# kolrs868_tx.net
KiCad netlist of a schematic drawn in EAGLE
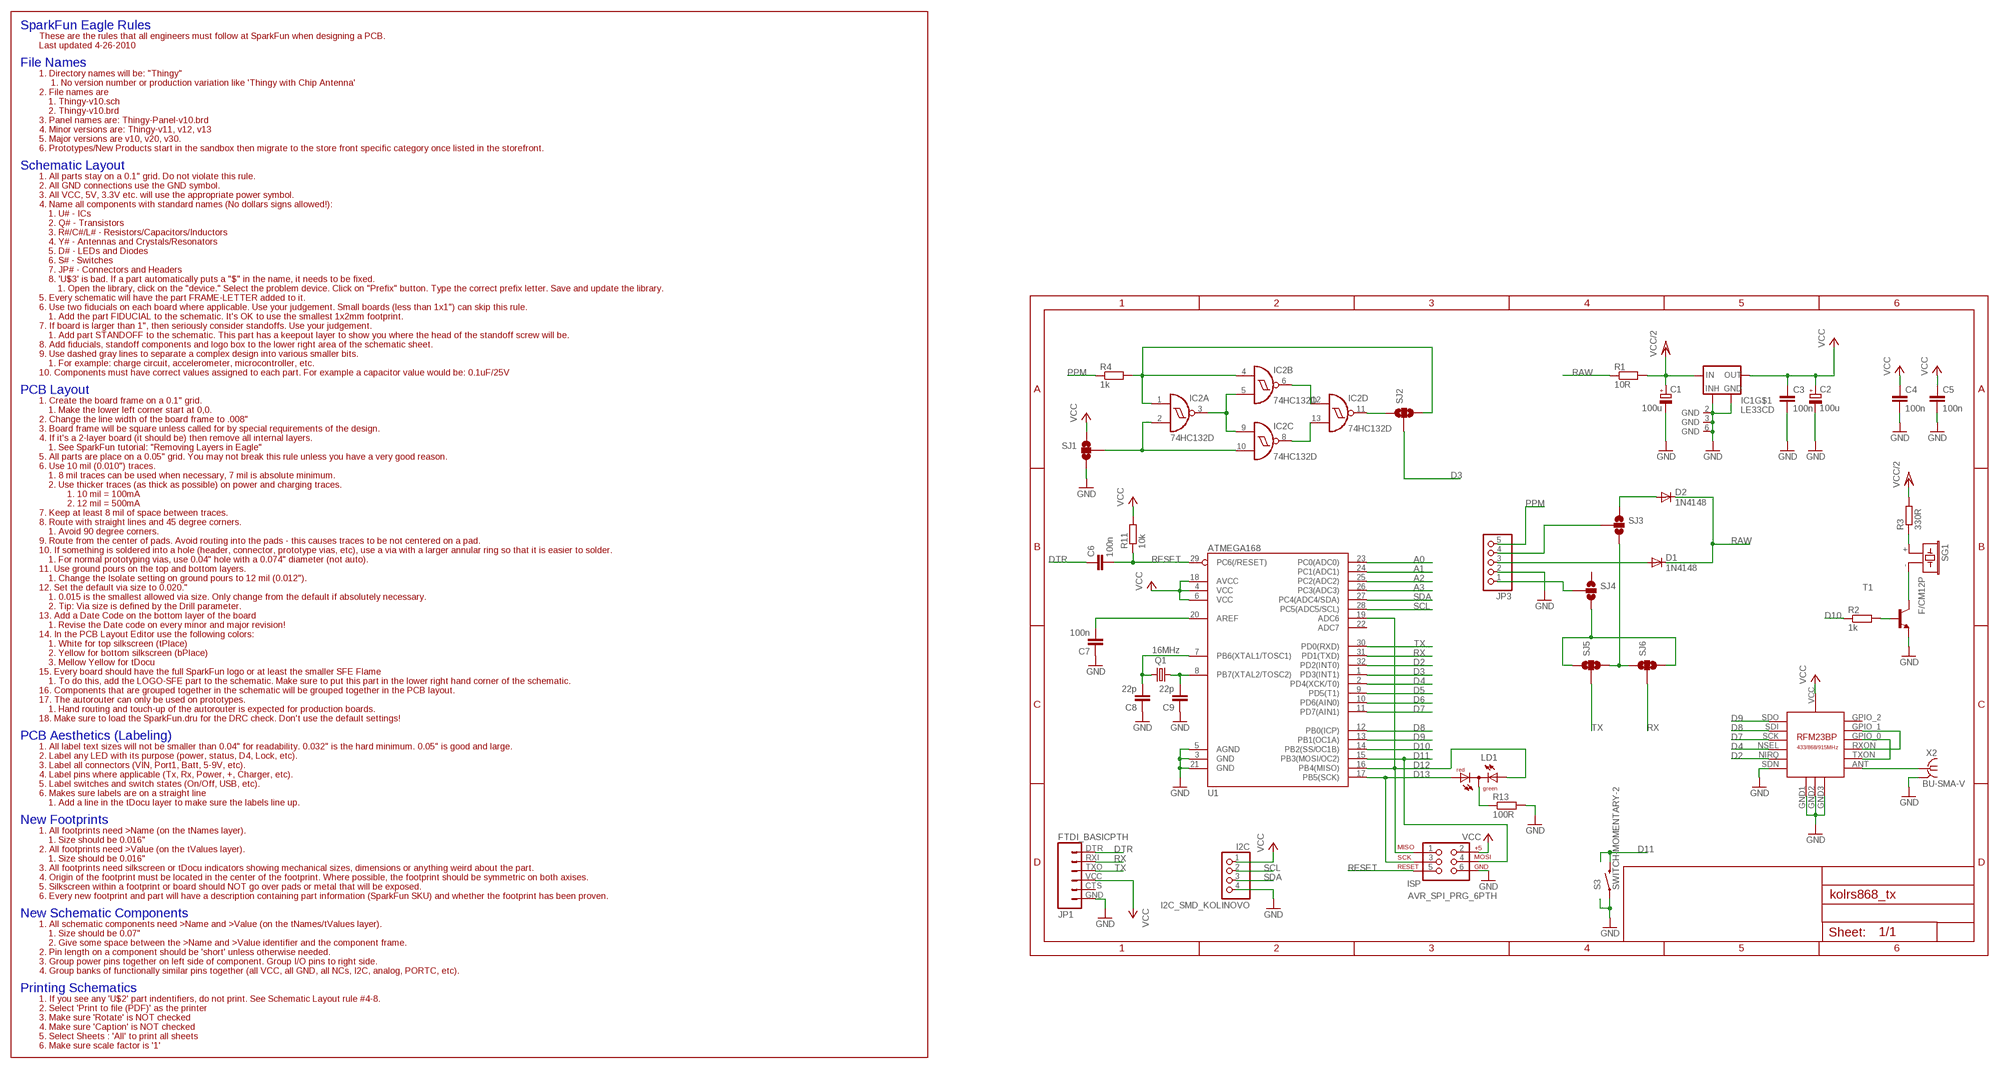
[diagram p0: schematic, sheet 1]

(export (version "E")
  (design (tool "Eeschema 10.0.6"))
  (components
    (comp (ref "C1")
      (value "100u")
      (footprint "eagle-import:SMC_B")
      (libsource (lib "eagle-import") (part "CPOL-EUSMCB"))
    )
    (comp (ref "C2")
      (value "100u")
      (footprint "eagle-import:SMC_B")
      (libsource (lib "eagle-import") (part "CPOL-EUSMCB"))
    )
    (comp (ref "C3")
      (value "100n")
      (footprint "eagle-import:M0805")
      (libsource (lib "eagle-import") (part "C-EU_KOLIN"))
    )
    (comp (ref "C4")
      (value "100n")
      (footprint "eagle-import:M0805")
      (libsource (lib "eagle-import") (part "C-EU_KOLIN"))
    )
    (comp (ref "C5")
      (value "100n")
      (footprint "eagle-import:M0805")
      (libsource (lib "eagle-import") (part "C-EU_KOLIN"))
    )
    (comp (ref "C6")
      (value "100n")
      (footprint "eagle-import:M0805")
      (libsource (lib "eagle-import") (part "C-EU_KOLIN"))
    )
    (comp (ref "C7")
      (value "100n")
      (footprint "eagle-import:M0805")
      (libsource (lib "eagle-import") (part "C-EU_KOLIN"))
    )
    (comp (ref "C8")
      (value "22p")
      (footprint "eagle-import:M0805")
      (libsource (lib "eagle-import") (part "C-EU_KOLIN"))
    )
    (comp (ref "C9")
      (value "22p")
      (footprint "eagle-import:M0805")
      (libsource (lib "eagle-import") (part "C-EU_KOLIN"))
    )
    (comp (ref "D1")
      (value "1N4148")
      (footprint "eagle-import:MINIMELF")
      (libsource (lib "eagle-import") (part "DIODE-MINIMELF"))
    )
    (comp (ref "D2")
      (value "1N4148")
      (footprint "eagle-import:MINIMELF")
      (libsource (lib "eagle-import") (part "DIODE-MINIMELF"))
    )
    (comp (ref "I2C")
      (value "I2C_SMD_KOLINOVO")
      (footprint "eagle-import:1X04")
      (libsource (lib "eagle-import") (part "I2C_SMD_KOLINOVO"))
    )
    (comp (ref "IC1")
      (value "LE33CD")
      (footprint "eagle-import:SO8")
      (libsource (lib "eagle-import") (part "LE33CD"))
    )
    (comp (ref "IC2")
      (value "74HC132D")
      (footprint "eagle-import:SO14")
      (libsource (lib "eagle-import") (part "74132DHC"))
    )
    (comp (ref "ISP")
      (value "AVR_SPI_PRG_6PTH")
      (footprint "eagle-import:2X3")
      (libsource (lib "eagle-import") (part "AVR_SPI_PRG_6PTH"))
    )
    (comp (ref "JP1")
      (value "FTDI_BASICPTH")
      (footprint "eagle-import:FTDI_BASIC")
      (libsource (lib "eagle-import") (part "FTDI_BASICPTH"))
    )
    (comp (ref "JP3")
      (value "PINHD-1X5")
      (footprint "eagle-import:1X05")
      (libsource (lib "eagle-import") (part "PINHD-1X5"))
    )
    (comp (ref "LD1")
      (value "DUOLED-RG-C")
      (footprint "eagle-import:DUOLED-C-5MM")
      (libsource (lib "eagle-import") (part "DUOLED-RG-C"))
    )
    (comp (ref "Q1")
      (value "16MHz")
      (footprint "eagle-import:HC49UP")
      (libsource (lib "eagle-import") (part "CRYSTALHC49UP"))
    )
    (comp (ref "R1")
      (value "10R")
      (footprint "eagle-import:M0805")
      (libsource (lib "eagle-import") (part "R-EU_KOLINM0805"))
    )
    (comp (ref "R2")
      (value "1k")
      (footprint "eagle-import:M0805")
      (libsource (lib "eagle-import") (part "R-EU_KOLINM0805"))
    )
    (comp (ref "R3")
      (value "330R")
      (footprint "eagle-import:M0805")
      (libsource (lib "eagle-import") (part "R-EU_KOLINM0805"))
    )
    (comp (ref "R4")
      (value "1k")
      (footprint "eagle-import:M0805")
      (libsource (lib "eagle-import") (part "R-EU_KOLINM0805"))
    )
    (comp (ref "R11")
      (value "10k")
      (footprint "eagle-import:M0805")
      (libsource (lib "eagle-import") (part "R-EU_KOLINM0805"))
    )
    (comp (ref "R13")
      (value "100R")
      (footprint "eagle-import:M0805")
      (libsource (lib "eagle-import") (part "R-EU_KOLINM0805"))
    )
    (comp (ref "S3")
      (value "SWITCH-MOMENTARY-2")
      (footprint "eagle-import:TACTILE_SWITCH_TALL")
      (libsource (lib "eagle-import") (part "SWITCH-MOMENTARY-2"))
    )
    (comp (ref "SG1")
      (value "F/CM12P")
      (footprint "eagle-import:F_CM12P")
      (libsource (lib "eagle-import") (part "F/CM12P"))
    )
    (comp (ref "SJ1")
      (value "SOLDERJUMPER_2WAYS")
      (footprint "eagle-import:SJ_3")
      (libsource (lib "eagle-import") (part "SOLDERJUMPER_2WAYS"))
    )
    (comp (ref "SJ2")
      (value "SOLDERJUMPER_2WAYS")
      (footprint "eagle-import:SJ_3")
      (libsource (lib "eagle-import") (part "SOLDERJUMPER_2WAYS"))
    )
    (comp (ref "SJ3")
      (value "SOLDERJUMPER_2WAYS")
      (footprint "eagle-import:SJ_3")
      (libsource (lib "eagle-import") (part "SOLDERJUMPER_2WAYS"))
    )
    (comp (ref "SJ4")
      (value "SOLDERJUMPER_2WAYS")
      (footprint "eagle-import:SJ_3")
      (libsource (lib "eagle-import") (part "SOLDERJUMPER_2WAYS"))
    )
    (comp (ref "SJ5")
      (value "SOLDERJUMPER_2WAYS")
      (footprint "eagle-import:SJ_3")
      (libsource (lib "eagle-import") (part "SOLDERJUMPER_2WAYS"))
    )
    (comp (ref "SJ6")
      (value "SOLDERJUMPER_2WAYS")
      (footprint "eagle-import:SJ_3")
      (libsource (lib "eagle-import") (part "SOLDERJUMPER_2WAYS"))
    )
    (comp (ref "T1")
      (value "BC848-NPN-SOT23-BEC")
      (footprint "eagle-import:SOT23-BEC")
      (libsource (lib "eagle-import") (part "-NPN-SOT23-BECBC848"))
    )
    (comp (ref "U$3")
      (value "RFM23BP")
      (footprint "eagle-import:RFM23BP")
      (libsource (lib "eagle-import") (part "RFM23BP"))
    )
    (comp (ref "U1")
      (value "ATMEGA168")
      (footprint "eagle-import:TQFP32-08")
      (libsource (lib "eagle-import") (part "ATMEGA168"))
    )
    (comp (ref "X2")
      (value "BU-SMA-V")
      (footprint "eagle-import:BU-SMA-V")
      (libsource (lib "eagle-import") (part "BU-SMA-V"))
    )
  )
  (nets
    (net (code "1") (name "/A0") (class "Default")
      (node (ref "U1") (pin "23") (pinfunction "PC0(ADC0)_23") (pintype "bidirectional"))
    )
    (net (code "2") (name "/A1") (class "Default")
      (node (ref "U1") (pin "24") (pinfunction "PC1(ADC1)_24") (pintype "bidirectional"))
    )
    (net (code "3") (name "/A2") (class "Default")
      (node (ref "U1") (pin "25") (pinfunction "PC2(ADC2)_25") (pintype "bidirectional"))
    )
    (net (code "4") (name "/A3") (class "Default")
      (node (ref "U1") (pin "26") (pinfunction "PC3(ADC3)_26") (pintype "bidirectional"))
    )
    (net (code "5") (name "/D2") (class "Default")
      (node (ref "U$3") (pin "NIRQ") (pinfunction "NIRQ_NIRQ") (pintype "bidirectional"))
      (node (ref "U1") (pin "32") (pinfunction "PD2(INT0)_32") (pintype "bidirectional"))
    )
    (net (code "6") (name "/D3") (class "Default")
      (node (ref "SJ2") (pin "2") (pinfunction "2_2") (pintype "passive"))
      (node (ref "U1") (pin "1") (pinfunction "PD3(INT1)_1") (pintype "bidirectional"))
    )
    (net (code "7") (name "/D4") (class "Default")
      (node (ref "U$3") (pin "NSEL") (pinfunction "NSEL_NSEL") (pintype "bidirectional"))
      (node (ref "U1") (pin "2") (pinfunction "PD4(XCK/T0)_2") (pintype "bidirectional"))
    )
    (net (code "8") (name "/D5") (class "Default")
      (node (ref "U1") (pin "9") (pinfunction "PD5(T1)_9") (pintype "bidirectional"))
    )
    (net (code "9") (name "/D6") (class "Default")
      (node (ref "U1") (pin "10") (pinfunction "PD6(AIN0)_10") (pintype "bidirectional"))
    )
    (net (code "10") (name "/D7") (class "Default")
      (node (ref "U$3") (pin "SCK") (pinfunction "SCK_SCK") (pintype "bidirectional"))
      (node (ref "U1") (pin "11") (pinfunction "PD7(AIN1)_11") (pintype "bidirectional"))
    )
    (net (code "11") (name "/D8") (class "Default")
      (node (ref "U$3") (pin "SDI") (pinfunction "SDI_SDI") (pintype "bidirectional"))
      (node (ref "U1") (pin "12") (pinfunction "PB0(ICP)_12") (pintype "bidirectional"))
    )
    (net (code "12") (name "/D9") (class "Default")
      (node (ref "U$3") (pin "SDO") (pinfunction "SDO_SDO") (pintype "bidirectional"))
      (node (ref "U1") (pin "13") (pinfunction "PB1(OC1A)_13") (pintype "bidirectional"))
    )
    (net (code "13") (name "/D10") (class "Default")
      (node (ref "R2") (pin "1") (pinfunction "1_1") (pintype "passive"))
      (node (ref "U1") (pin "14") (pinfunction "PB2(SS/OC1B)_14") (pintype "bidirectional"))
    )
    (net (code "14") (name "/D11") (class "Default")
      (node (ref "ISP") (pin "4") (pinfunction "4_4") (pintype "passive"))
      (node (ref "S3") (pin "B2") (pinfunction "2_B2") (pintype "passive"))
      (node (ref "U1") (pin "15") (pinfunction "PB3(MOSI/OC2)_15") (pintype "bidirectional"))
    )
    (net (code "15") (name "/D12") (class "Default")
      (node (ref "ISP") (pin "1") (pinfunction "1_1") (pintype "passive"))
      (node (ref "LD1") (pin "AX") (pinfunction "AG_AX") (pintype "passive"))
      (node (ref "U1") (pin "16") (pinfunction "PB4(MISO)_16") (pintype "bidirectional"))
      (node (ref "U1") (pin "19") (pinfunction "ADC6_19") (pintype "bidirectional"))
    )
    (net (code "16") (name "/D13") (class "Default")
      (node (ref "ISP") (pin "3") (pinfunction "3_3") (pintype "passive"))
      (node (ref "LD1") (pin "AR") (pinfunction "AR_AR") (pintype "passive"))
      (node (ref "U1") (pin "17") (pinfunction "PB5(SCK)_17") (pintype "bidirectional"))
    )
    (net (code "17") (name "/DTR") (class "Default")
      (node (ref "C6") (pin "1") (pinfunction "1_1") (pintype "passive"))
      (node (ref "JP1") (pin "DTR") (pinfunction "1_DTR") (pintype "passive"))
    )
    (net (code "18") (name "/PPM") (class "Default")
      (node (ref "JP3") (pin "5") (pinfunction "5_5") (pintype "passive"))
      (node (ref "R4") (pin "1") (pinfunction "1_1") (pintype "passive"))
    )
    (net (code "19") (name "/RAW") (class "Default")
      (node (ref "D1") (pin "C") (pinfunction "C_C") (pintype "passive"))
      (node (ref "D2") (pin "C") (pinfunction "C_C") (pintype "passive"))
      (node (ref "R1") (pin "1") (pinfunction "1_1") (pintype "passive"))
    )
    (net (code "20") (name "/RESET") (class "Default")
      (node (ref "C6") (pin "2") (pinfunction "2_2") (pintype "passive"))
      (node (ref "ISP") (pin "5") (pinfunction "5_5") (pintype "passive"))
      (node (ref "R11") (pin "1") (pinfunction "1_1") (pintype "passive"))
      (node (ref "U1") (pin "29") (pinfunction "PC6(/RESET)_29") (pintype "bidirectional"))
    )
    (net (code "21") (name "/RX") (class "Default")
      (node (ref "JP1") (pin "RXI") (pinfunction "2_RXI") (pintype "passive"))
      (node (ref "SJ6") (pin "2") (pinfunction "2_2") (pintype "passive"))
      (node (ref "U1") (pin "31") (pinfunction "PD1(TXD)_31") (pintype "bidirectional"))
    )
    (net (code "22") (name "/SCL") (class "Default")
      (node (ref "I2C") (pin "2") (pinfunction "2_2") (pintype "passive"))
      (node (ref "U1") (pin "28") (pinfunction "PC5(ADC5/SCL)_28") (pintype "bidirectional"))
    )
    (net (code "23") (name "/SDA") (class "Default")
      (node (ref "I2C") (pin "3") (pinfunction "3_3") (pintype "passive"))
      (node (ref "U1") (pin "27") (pinfunction "PC4(ADC4/SDA)_27") (pintype "bidirectional"))
    )
    (net (code "24") (name "/TX") (class "Default")
      (node (ref "JP1") (pin "TXO") (pinfunction "3_TXO") (pintype "passive"))
      (node (ref "SJ5") (pin "2") (pinfunction "2_2") (pintype "passive"))
      (node (ref "U1") (pin "30") (pinfunction "PD0(RXD)_30") (pintype "bidirectional"))
    )
    (net (code "25") (name "GND") (class "Default")
      (node (ref "C1") (pin "-") (pinfunction "-_-") (pintype "passive"))
      (node (ref "C2") (pin "-") (pinfunction "-_-") (pintype "passive"))
      (node (ref "C3") (pin "2") (pinfunction "2_2") (pintype "passive"))
      (node (ref "C4") (pin "2") (pinfunction "2_2") (pintype "passive"))
      (node (ref "C5") (pin "2") (pinfunction "2_2") (pintype "passive"))
      (node (ref "C7") (pin "1") (pinfunction "1_1") (pintype "passive"))
      (node (ref "C8") (pin "1") (pinfunction "1_1") (pintype "passive"))
      (node (ref "C9") (pin "1") (pinfunction "1_1") (pintype "passive"))
      (node (ref "I2C") (pin "4") (pinfunction "4_4") (pintype "passive"))
      (node (ref "IC1") (pin "2") (pinfunction "GND_2") (pintype "power_in"))
      (node (ref "IC1") (pin "3") (pinfunction "GND_3") (pintype "power_in"))
      (node (ref "IC1") (pin "5") (pinfunction "INHIBIT_5") (pintype "input"))
      (node (ref "IC1") (pin "6") (pinfunction "GND_6") (pintype "power_in"))
      (node (ref "IC1") (pin "7") (pinfunction "GND_7") (pintype "input"))
      (node (ref "ISP") (pin "6") (pinfunction "6_6") (pintype "passive"))
      (node (ref "JP1") (pin "GND") (pinfunction "6_GND") (pintype "passive"))
      (node (ref "JP3") (pin "2") (pinfunction "2_2") (pintype "passive"))
      (node (ref "R13") (pin "2") (pinfunction "2_2") (pintype "passive"))
      (node (ref "S3") (pin "A2") (pinfunction "1_A2") (pintype "passive"))
      (node (ref "SJ1") (pin "3") (pinfunction "3_3") (pintype "passive"))
      (node (ref "T1") (pin "E") (pinfunction "E_E") (pintype "passive"))
      (node (ref "U$3") (pin "GND1") (pinfunction "GND1_GND1") (pintype "power_in"))
      (node (ref "U$3") (pin "GND2") (pinfunction "GND2_GND2") (pintype "power_in"))
      (node (ref "U$3") (pin "GND3") (pinfunction "GND3_GND3") (pintype "power_in"))
      (node (ref "U$3") (pin "SDN") (pinfunction "SDN_SDN") (pintype "bidirectional"))
      (node (ref "U1") (pin "21") (pinfunction "GND_21") (pintype "bidirectional"))
      (node (ref "U1") (pin "3") (pinfunction "GND_3") (pintype "bidirectional"))
      (node (ref "U1") (pin "5") (pinfunction "AGND_5") (pintype "bidirectional"))
      (node (ref "X2") (pin "2") (pinfunction "GND_2") (pintype "power_in"))
    )
    (net (code "26") (name "Net-(D1-PadA)") (class "Default")
      (node (ref "D1") (pin "A") (pinfunction "A_A") (pintype "passive"))
      (node (ref "JP3") (pin "3") (pinfunction "3_3") (pintype "passive"))
    )
    (net (code "27") (name "Net-(D2-PadA)") (class "Default")
      (node (ref "D2") (pin "A") (pinfunction "A_A") (pintype "passive"))
      (node (ref "SJ3") (pin "1") (pinfunction "1_1") (pintype "passive"))
    )
    (net (code "28") (name "Net-(IC2A-I0)") (class "Default")
      (node (ref "IC2") (pin "1") (pinfunction "I0_1") (pintype "input"))
      (node (ref "IC2") (pin "4") (pinfunction "I0_4") (pintype "input"))
      (node (ref "R4") (pin "2") (pinfunction "2_2") (pintype "passive"))
      (node (ref "SJ2") (pin "3") (pinfunction "3_3") (pintype "passive"))
    )
    (net (code "29") (name "Net-(IC2A-I1)") (class "Default")
      (node (ref "IC2") (pin "10") (pinfunction "I1_10") (pintype "input"))
      (node (ref "IC2") (pin "2") (pinfunction "I1_2") (pintype "input"))
      (node (ref "SJ1") (pin "2") (pinfunction "2_2") (pintype "passive"))
    )
    (net (code "30") (name "Net-(IC2A-O)") (class "Default")
      (node (ref "IC2") (pin "3") (pinfunction "O_3") (pintype "output"))
      (node (ref "IC2") (pin "5") (pinfunction "I1_5") (pintype "input"))
      (node (ref "IC2") (pin "9") (pinfunction "I0_9") (pintype "input"))
    )
    (net (code "31") (name "Net-(IC2B-O)") (class "Default")
      (node (ref "IC2") (pin "12") (pinfunction "I0_12") (pintype "input"))
      (node (ref "IC2") (pin "6") (pinfunction "O_6") (pintype "output"))
    )
    (net (code "32") (name "Net-(IC2C-O)") (class "Default")
      (node (ref "IC2") (pin "13") (pinfunction "I1_13") (pintype "input"))
      (node (ref "IC2") (pin "8") (pinfunction "O_8") (pintype "output"))
    )
    (net (code "33") (name "Net-(IC2D-O)") (class "Default")
      (node (ref "IC2") (pin "11") (pinfunction "O_11") (pintype "output"))
      (node (ref "SJ2") (pin "1") (pinfunction "1_1") (pintype "passive"))
    )
    (net (code "34") (name "Net-(JP3-Pad1)") (class "Default")
      (node (ref "JP3") (pin "1") (pinfunction "1_1") (pintype "passive"))
      (node (ref "SJ4") (pin "2") (pinfunction "2_2") (pintype "passive"))
    )
    (net (code "35") (name "Net-(JP3-Pad4)") (class "Default")
      (node (ref "JP3") (pin "4") (pinfunction "4_4") (pintype "passive"))
      (node (ref "SJ3") (pin "2") (pinfunction "2_2") (pintype "passive"))
    )
    (net (code "36") (name "Net-(LD1-PadC)") (class "Default")
      (node (ref "LD1") (pin "C") (pinfunction "C_C") (pintype "passive"))
      (node (ref "R13") (pin "1") (pinfunction "1_1") (pintype "passive"))
    )
    (net (code "37") (name "Net-(R2-Pad2)") (class "Default")
      (node (ref "R2") (pin "2") (pinfunction "2_2") (pintype "passive"))
      (node (ref "T1") (pin "B") (pinfunction "B_B") (pintype "passive"))
    )
    (net (code "38") (name "Net-(SG1-1)") (class "Default")
      (node (ref "R3") (pin "1") (pinfunction "1_1") (pintype "passive"))
      (node (ref "SG1") (pin "+") (pinfunction "1_+") (pintype "passive"))
    )
    (net (code "39") (name "Net-(SG1-2)") (class "Default")
      (node (ref "SG1") (pin "-") (pinfunction "2_-") (pintype "passive"))
      (node (ref "T1") (pin "C") (pinfunction "C_C") (pintype "passive"))
    )
    (net (code "40") (name "Net-(SJ3-Pad3)") (class "Default")
      (node (ref "SJ3") (pin "3") (pinfunction "3_3") (pintype "passive"))
      (node (ref "SJ5") (pin "3") (pinfunction "3_3") (pintype "passive"))
      (node (ref "SJ6") (pin "1") (pinfunction "1_1") (pintype "passive"))
    )
    (net (code "41") (name "Net-(SJ4-Pad3)") (class "Default")
      (node (ref "SJ4") (pin "3") (pinfunction "3_3") (pintype "passive"))
      (node (ref "SJ5") (pin "1") (pinfunction "1_1") (pintype "passive"))
      (node (ref "SJ6") (pin "3") (pinfunction "3_3") (pintype "passive"))
    )
    (net (code "42") (name "Net-(U$3-PadANT)") (class "Default")
      (node (ref "U$3") (pin "ANT") (pinfunction "ANT_ANT") (pintype "bidirectional"))
      (node (ref "X2") (pin "1") (pinfunction "1_1") (pintype "passive"))
    )
    (net (code "43") (name "Net-(U$3-PadGPIO_0)") (class "Default")
      (node (ref "U$3") (pin "GPIO_0") (pinfunction "GPIO_0_GPIO_0") (pintype "bidirectional"))
      (node (ref "U$3") (pin "TXON") (pinfunction "TXON_TXON") (pintype "bidirectional"))
    )
    (net (code "44") (name "Net-(U$3-PadGPIO_1)") (class "Default")
      (node (ref "U$3") (pin "GPIO_1") (pinfunction "GPIO_1_GPIO_1") (pintype "bidirectional"))
      (node (ref "U$3") (pin "RXON") (pinfunction "RXON_RXON") (pintype "bidirectional"))
    )
    (net (code "45") (name "Net-(U1-AREF)") (class "Default")
      (node (ref "C7") (pin "2") (pinfunction "2_2") (pintype "passive"))
      (node (ref "U1") (pin "20") (pinfunction "AREF_20") (pintype "bidirectional"))
    )
    (net (code "46") (name "Net-(U1-PB6(XTAL1{slash}TOSC1))") (class "Default")
      (node (ref "C8") (pin "2") (pinfunction "2_2") (pintype "passive"))
      (node (ref "Q1") (pin "2") (pinfunction "2_2") (pintype "passive"))
      (node (ref "U1") (pin "7") (pinfunction "PB6(XTAL1/TOSC1)_7") (pintype "bidirectional"))
    )
    (net (code "47") (name "Net-(U1-PB7(XTAL2{slash}TOSC2))") (class "Default")
      (node (ref "C9") (pin "2") (pinfunction "2_2") (pintype "passive"))
      (node (ref "Q1") (pin "1") (pinfunction "1_1") (pintype "passive"))
      (node (ref "U1") (pin "8") (pinfunction "PB7(XTAL2/TOSC2)_8") (pintype "bidirectional"))
    )
    (net (code "48") (name "VCC") (class "Default")
      (node (ref "C2") (pin "+") (pinfunction "+_+") (pintype "passive"))
      (node (ref "C3") (pin "1") (pinfunction "1_1") (pintype "passive"))
      (node (ref "C4") (pin "1") (pinfunction "1_1") (pintype "passive"))
      (node (ref "C5") (pin "1") (pinfunction "1_1") (pintype "passive"))
      (node (ref "I2C") (pin "1") (pinfunction "1_1") (pintype "passive"))
      (node (ref "IC1") (pin "1") (pinfunction "OUT_1") (pintype "passive"))
      (node (ref "ISP") (pin "2") (pinfunction "2_2") (pintype "passive"))
      (node (ref "JP1") (pin "VCC") (pinfunction "4_VCC") (pintype "passive"))
      (node (ref "R11") (pin "2") (pinfunction "2_2") (pintype "passive"))
      (node (ref "SJ1") (pin "1") (pinfunction "1_1") (pintype "passive"))
      (node (ref "U$3") (pin "VCC") (pinfunction "VCC_VCC") (pintype "power_in"))
      (node (ref "U1") (pin "18") (pinfunction "AVCC_18") (pintype "bidirectional"))
      (node (ref "U1") (pin "4") (pinfunction "VCC_4") (pintype "bidirectional"))
      (node (ref "U1") (pin "6") (pinfunction "VCC_6") (pintype "bidirectional"))
    )
    (net (code "49") (name "VCC{slash}2") (class "Default")
      (node (ref "C1") (pin "+") (pinfunction "+_+") (pintype "passive"))
      (node (ref "IC1") (pin "8") (pinfunction "IN_8") (pintype "input"))
      (node (ref "R1") (pin "2") (pinfunction "2_2") (pintype "passive"))
      (node (ref "R3") (pin "2") (pinfunction "2_2") (pintype "passive"))
    )
    (net (code "50") (name "unconnected-(JP1-5-PadCTS)") (class "Default")
      (node (ref "JP1") (pin "CTS") (pinfunction "5_CTS") (pintype "passive"))
    )
    (net (code "51") (name "unconnected-(SJ4-Pad1)") (class "Default")
      (node (ref "SJ4") (pin "1") (pinfunction "1_1") (pintype "passive"))
    )
    (net (code "52") (name "unconnected-(U$3-PadGPIO_2)") (class "Default")
      (node (ref "U$3") (pin "GPIO_2") (pinfunction "GPIO_2_GPIO_2") (pintype "bidirectional"))
    )
    (net (code "53") (name "unconnected-(U1-ADC7-Pad22)") (class "Default")
      (node (ref "U1") (pin "22") (pinfunction "ADC7_22") (pintype "bidirectional"))
    )
  )
)
